# pump-board.net
KiCad netlist of a schematic drawn in EAGLE
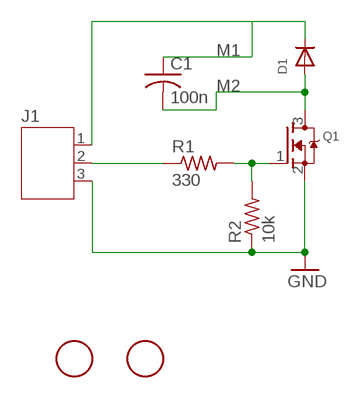
[diagram p0: schematic, sheet 1]

(export (version "E")
  (design (tool "Eeschema 10.0.6"))
  (components
    (comp (ref "C1")
      (value "100n")
      (footprint "eagle-import:C1206")
      (libsource (lib "eagle-import") (part "C-USC1206"))
    )
    (comp (ref "D1")
      (value "DIODESOD-123")
      (footprint "eagle-import:SOD-123")
      (libsource (lib "eagle-import") (part "DIODESOD-123"))
    )
    (comp (ref "J1")
      (value "JST-PH3")
      (footprint "eagle-import:JST-PH3")
      (libsource (lib "eagle-import") (part "JST-PH3"))
    )
    (comp (ref "Q1")
      (value "MOSFET-NREFLOW")
      (footprint "eagle-import:SOT23")
      (libsource (lib "eagle-import") (part "MOSFET-NREFLOW"))
    )
    (comp (ref "R1")
      (value "330")
      (footprint "eagle-import:R1206")
      (libsource (lib "eagle-import") (part "R-US_R1206"))
    )
    (comp (ref "R2")
      (value "10k")
      (footprint "eagle-import:R1206")
      (libsource (lib "eagle-import") (part "R-US_R1206"))
    )
    (comp (ref "U$1")
      (value "FIDUCIAL")
      (footprint "eagle-import:FIDUCIAL_1MM")
      (libsource (lib "eagle-import") (part "FIDUCIAL"))
    )
    (comp (ref "U$2")
      (value "FIDUCIAL")
      (footprint "eagle-import:FIDUCIAL_1MM")
      (libsource (lib "eagle-import") (part "FIDUCIAL"))
    )
  )
  (nets
    (net (code "1") (name "/M1") (class "Default")
      (node (ref "C1") (pin "1") (pinfunction "1_1") (pintype "passive"))
      (node (ref "D1") (pin "C") (pinfunction "C_C") (pintype "passive"))
      (node (ref "J1") (pin "1") (pinfunction "1_1") (pintype "passive"))
    )
    (net (code "2") (name "/M2") (class "Default")
      (node (ref "C1") (pin "2") (pinfunction "2_2") (pintype "passive"))
      (node (ref "D1") (pin "A") (pinfunction "A_A") (pintype "passive"))
      (node (ref "Q1") (pin "3") (pinfunction "D_3") (pintype "bidirectional"))
    )
    (net (code "3") (name "GND") (class "Default")
      (node (ref "J1") (pin "3") (pinfunction "3_3") (pintype "passive"))
      (node (ref "Q1") (pin "2") (pinfunction "S_2") (pintype "bidirectional"))
      (node (ref "R2") (pin "1") (pinfunction "1_1") (pintype "passive"))
    )
    (net (code "4") (name "Net-(J1-Pad2)") (class "Default")
      (node (ref "J1") (pin "2") (pinfunction "2_2") (pintype "passive"))
      (node (ref "R1") (pin "1") (pinfunction "1_1") (pintype "passive"))
    )
    (net (code "5") (name "Net-(Q1-G)") (class "Default")
      (node (ref "Q1") (pin "1") (pinfunction "G_1") (pintype "bidirectional"))
      (node (ref "R1") (pin "2") (pinfunction "2_2") (pintype "passive"))
      (node (ref "R2") (pin "2") (pinfunction "2_2") (pintype "passive"))
    )
  )
)
